# POWER.net
KiCad netlist of a schematic drawn in Altium Designer
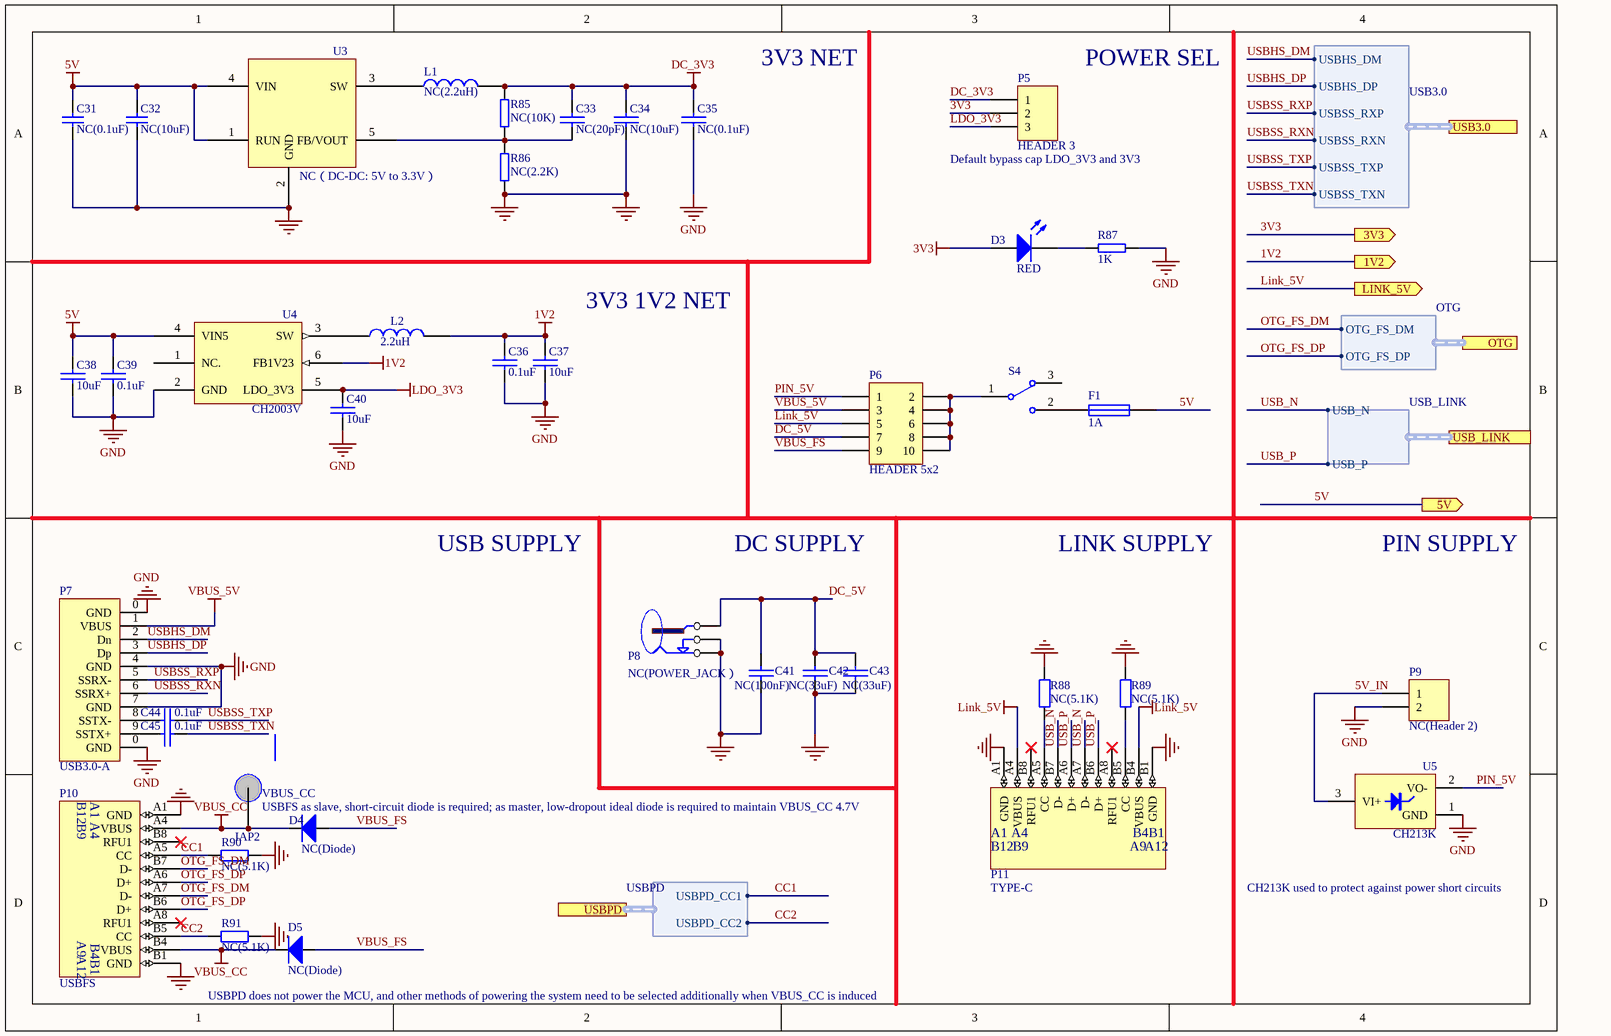
[diagram p0: POWER.SchDoc]

(export (version "E")
  (design (tool "Eeschema 10.0.6"))
  (components
    (comp (ref "C31")
      (value "NC(0.1uF)")
      (footprint "0402_C")
      (description "Capacitor")
      (fields (field (name "PUBLISHER") "Altium Limited"))
      (libsource (lib "Miscellaneous Devices") (part "Cap"))
    )
    (comp (ref "C32")
      (value "NC(10uF)")
      (footprint "0603_C")
      (description "Capacitor")
      (fields (field (name "PUBLISHER") "Altium Limited"))
      (libsource (lib "Miscellaneous Devices") (part "Cap"))
    )
    (comp (ref "C33")
      (value "NC(20pF)")
      (footprint "0402_C")
      (description "Capacitor")
      (libsource (lib "*") (part "CAP"))
    )
    (comp (ref "C34")
      (value "NC(10uF)")
      (footprint "0603_C")
      (description "Capacitor")
      (libsource (lib "*") (part "CAP"))
    )
    (comp (ref "C35")
      (value "NC(0.1uF)")
      (footprint "0402_C")
      (description "Capacitor")
      (libsource (lib "*") (part "CAP"))
    )
    (comp (ref "C36")
      (value "0.1uF")
      (footprint "0402_C")
      (description "Capacitor")
      (libsource (lib "") (part "CAP_1"))
    )
    (comp (ref "C37")
      (value "10uF")
      (footprint "0603_C")
      (description "Capacitor")
      (libsource (lib "*") (part "CAP"))
    )
    (comp (ref "C38")
      (value "10uF")
      (footprint "0603_C")
      (description "Capacitor")
      (libsource (lib "*") (part "CAP"))
    )
    (comp (ref "C39")
      (value "0.1uF")
      (footprint "0402_C")
      (description "Capacitor")
      (libsource (lib "") (part "CAP_1"))
    )
    (comp (ref "C40")
      (value "10uF")
      (footprint "0603_C")
      (description "Capacitor")
      (libsource (lib "*") (part "CAP"))
    )
    (comp (ref "C41")
      (value "NC(100nF)")
      (footprint "0402_C")
      (description "Capacitor")
      (libsource (lib "*") (part "CAP"))
    )
    (comp (ref "C42")
      (value "NC(33uF)")
      (footprint "3528_C")
      (description "Capacitor")
      (libsource (lib "*") (part "CAP"))
    )
    (comp (ref "C43")
      (value "NC(33uF)")
      (footprint "3528_C")
      (description "Capacitor")
      (libsource (lib "*") (part "CAP"))
    )
    (comp (ref "C44")
      (value "0.1uF")
      (footprint "0402_C")
      (description "Capacitor")
      (libsource (lib "*") (part "CAP"))
    )
    (comp (ref "C45")
      (value "0.1uF")
      (footprint "0402_C")
      (description "Capacitor")
      (libsource (lib "*") (part "CAP"))
    )
    (comp (ref "D3")
      (value "RED")
      (footprint "0603+")
      (description "Typical INFRARED GaAs LED")
      (fields (field (name "PUBLISHER") "Altium Limited"))
      (libsource (lib "*") (part "LED0"))
    )
    (comp (ref "D4")
      (value "NC(Diode)")
      (footprint "SOD-323")
      (description "Default Diode")
      (libsource (lib "wch_sch_others") (part "Diode"))
    )
    (comp (ref "D5")
      (value "NC(Diode)")
      (footprint "SOD-323")
      (description "Default Diode")
      (libsource (lib "wch_sch_others") (part "Diode"))
    )
    (comp (ref "F1")
      (value "1A")
      (footprint "0805")
      (description "Fuse")
      (libsource (lib "*") (part "FUSE1"))
    )
    (comp (ref "IAP2")
      (value "VBUS_CC")
      (footprint "TESTPOINT1")
      (description "测试点")
      (libsource (lib "wch_sch_others") (part "Testpoint"))
    )
    (comp (ref "L1") (value "NC(2.2uH)") (footprint "CD32") (libsource (lib "*") (part "INDUCTOR")))
    (comp (ref "L2") (value "2.2uH") (footprint "CD32") (libsource (lib "*") (part "INDUCTOR")))
    (comp (ref "P5")
      (value "HEADER 3")
      (footprint "SIP3-2.54MM")
      (description "Header, 3-Pin")
      (libsource (lib "wch_sch_others") (part "HEADER 3"))
    )
    (comp (ref "P6")
      (value "HEADER 5x2")
      (footprint "MYPCB:IDC10-2.54mm")
      (description "Header, 5-Pin, Dual row")
      (libsource (lib "wch_sch_others") (part "HEADER 5x2"))
    )
    (comp (ref "P7")
      (value "USB3.0-A")
      (footprint "USB3.0-A-Receptacle")
      (libsource (lib "wch_sch_others") (part "USB3.0-A"))
    )
    (comp (ref "P8") (value "NC(POWER_JACK）") (footprint "DC-005") (libsource (lib "*") (part "POWER_JACK")))
    (comp (ref "P9")
      (value "NC(Header 2)")
      (footprint "SIP2-2.54mm")
      (description "Header, 2-Pin")
      (fields (field (name "PUBLISHER") "Altium Limited"))
      (libsource (lib "*") (part "Header 2"))
    )
    (comp (ref "P10")
      (value "USBFS")
      (footprint "TYPE-C-Receptacle-2.0")
      (libsource (lib "*") (part "TYPE-C1"))
    )
    (comp (ref "P11")
      (value "TYPE-C")
      (footprint "TYPE-C-Receptacle-2.0")
      (libsource (lib "") (part "TYPE-C1_1"))
    )
    (comp (ref "R85") (value "NC(10K)") (footprint "0402") (libsource (lib "*") (part "R")))
    (comp (ref "R86") (value "NC(2.2K)") (footprint "0402") (libsource (lib "*") (part "R")))
    (comp (ref "R87") (value "1K") (footprint "0402") (libsource (lib "wch_sch_others") (part "RES")))
    (comp (ref "R88")
      (value "NC(5.1K)")
      (footprint "0402")
      (description "Resistor")
      (libsource (lib "Miscellaneous Devices") (part "Res2"))
    )
    (comp (ref "R89")
      (value "NC(5.1K)")
      (footprint "0402")
      (description "Resistor")
      (libsource (lib "Miscellaneous Devices") (part "Res2"))
    )
    (comp (ref "R90")
      (value "NC(5.1K)")
      (footprint "0402")
      (description "Resistor")
      (libsource (lib "") (part "Res2_1"))
    )
    (comp (ref "R91")
      (value "NC(5.1K)")
      (footprint "0402")
      (description "Resistor")
      (libsource (lib "") (part "Res2_1"))
    )
    (comp (ref "S4")
      (value "SW-SPDT")
      (footprint "SW1")
      (description "SPDT Subminiature Toggle Switch, Right Angle Mounting, Vertical Actuation")
      (libsource (lib "*") (part "SW-SPDT"))
    )
    (comp (ref "U3")
      (value "NC（DC-DC: 5V to 3.3V）")
      (footprint "SOT-23-5")
      (libsource (lib "SCH") (part "8503AM"))
    )
    (comp (ref "U4")
      (value "CH2003V")
      (footprint "SOT-23-6")
      (description "Step-Down DC-DC Converter, 5V input, 1.23V * 700mA output, with LDO 3.3V * 160mA")
      (libsource (lib "DHXXXSCH") (part "CH2003V"))
    )
    (comp (ref "U5")
      (value "CH213K")
      (footprint "SOT-23-3")
      (description "Ideal Diode 5V*1A")
      (libsource (lib "*") (part "CH213K"))
    )
  )
  (nets
    (net (code "5") (name "/5V_IN") (class "Default")
      (node (ref "P9") (pin "1") (pinfunction "1_1") (pintype "passive"))
      (node (ref "U5") (pin "3") (pinfunction "VI+_3") (pintype "power_in"))
    )
    (net (code "6") (name "/CC1") (class "Default")
      (node (ref "P10") (pin "A5") (pinfunction "CC_A5") (pintype "bidirectional"))
      (node (ref "R90") (pin "1") (pinfunction "1_1") (pintype "passive"))
    )
    (net (code "7") (name "/CC2") (class "Default")
      (node (ref "P10") (pin "B5") (pinfunction "CC_B5") (pintype "bidirectional"))
      (node (ref "R91") (pin "1") (pinfunction "1_1") (pintype "passive"))
    )
    (net (code "8") (name "/DC_5V") (class "Default")
      (node (ref "C41") (pin "2") (pinfunction "2_2") (pintype "passive"))
      (node (ref "C42") (pin "2") (pinfunction "2_2") (pintype "passive"))
      (node (ref "C43") (pin "2") (pinfunction "2_2") (pintype "passive"))
      (node (ref "P6") (pin "7") (pinfunction "7_7") (pintype "passive"))
      (node (ref "P8") (pin "1") (pinfunction "V_1") (pintype "passive"))
    )
    (net (code "9") (name "/OTG_FS_DM") (class "Default")
      (node (ref "P10") (pin "A7") (pinfunction "D-_A7") (pintype "bidirectional"))
      (node (ref "P10") (pin "B7") (pinfunction "D-_B7") (pintype "bidirectional"))
    )
    (net (code "10") (name "/OTG_FS_DP") (class "Default")
      (node (ref "P10") (pin "A6") (pinfunction "D+_A6") (pintype "bidirectional"))
      (node (ref "P10") (pin "B6") (pinfunction "D+_B6") (pintype "bidirectional"))
    )
    (net (code "11") (name "/PIN_5V") (class "Default")
      (node (ref "P6") (pin "1") (pinfunction "1_1") (pintype "passive"))
      (node (ref "U5") (pin "2") (pinfunction "VO-_2") (pintype "power_in"))
    )
    (net (code "12") (name "/USBHS_DM") (class "Default")
      (node (ref "P7") (pin "2") (pinfunction "Dn_2") (pintype "passive"))
    )
    (net (code "13") (name "/USBHS_DP") (class "Default")
      (node (ref "P7") (pin "3") (pinfunction "Dp_3") (pintype "passive"))
    )
    (net (code "14") (name "/USBSS_RXN") (class "Default")
      (node (ref "P7") (pin "6") (pinfunction "SSRX+_6") (pintype "passive"))
    )
    (net (code "15") (name "/USBSS_RXP") (class "Default")
      (node (ref "P7") (pin "5") (pinfunction "SSRX-_5") (pintype "passive"))
    )
    (net (code "16") (name "/USBSS_TXN") (class "Default")
      (node (ref "C45") (pin "2") (pinfunction "2_2") (pintype "passive"))
    )
    (net (code "17") (name "/USBSS_TXP") (class "Default")
      (node (ref "C44") (pin "2") (pinfunction "2_2") (pintype "passive"))
    )
    (net (code "18") (name "/USB_N") (class "Default")
      (node (ref "P11") (pin "A7") (pinfunction "D-_A7") (pintype "bidirectional"))
      (node (ref "P11") (pin "B7") (pinfunction "D-_B7") (pintype "bidirectional"))
    )
    (net (code "19") (name "/USB_P") (class "Default")
      (node (ref "P11") (pin "A6") (pinfunction "D+_A6") (pintype "bidirectional"))
      (node (ref "P11") (pin "B6") (pinfunction "D+_B6") (pintype "bidirectional"))
    )
    (net (code "20") (name "/VBUS_FS") (class "Default")
      (node (ref "D4") (pin "1") (pinfunction "A_1") (pintype "passive"))
      (node (ref "D5") (pin "1") (pinfunction "A_1") (pintype "passive"))
      (node (ref "P6") (pin "9") (pinfunction "9_9") (pintype "passive"))
    )
    (net (code "25") (name "1V2") (class "Default")
      (node (ref "C36") (pin "2") (pinfunction "2_2") (pintype "passive"))
      (node (ref "C37") (pin "2") (pinfunction "2_2") (pintype "passive"))
      (node (ref "L2") (pin "2") (pinfunction "2_2") (pintype "passive"))
      (node (ref "U4") (pin "6") (pinfunction "FB1V23_6") (pintype "input"))
    )
    (net (code "26") (name "3V3") (class "Default")
      (node (ref "D3") (pin "1") (pinfunction "A_1") (pintype "passive"))
      (node (ref "P5") (pin "2") (pinfunction "2_2") (pintype "passive"))
    )
    (net (code "27") (name "5V") (class "Default")
      (node (ref "C31") (pin "2") (pinfunction "2_2") (pintype "passive"))
      (node (ref "C32") (pin "2") (pinfunction "2_2") (pintype "passive"))
      (node (ref "C38") (pin "2") (pinfunction "2_2") (pintype "passive"))
      (node (ref "C39") (pin "2") (pinfunction "2_2") (pintype "passive"))
      (node (ref "F1") (pin "1") (pinfunction "1_1") (pintype "passive"))
      (node (ref "U3") (pin "1") (pinfunction "RUN_1") (pintype "passive"))
      (node (ref "U3") (pin "4") (pinfunction "VIN_4") (pintype "passive"))
      (node (ref "U4") (pin "4") (pinfunction "VIN5_4") (pintype "power_in"))
    )
    (net (code "28") (name "DC_3V3") (class "Default")
      (node (ref "C33") (pin "1") (pinfunction "1_1") (pintype "passive"))
      (node (ref "C34") (pin "1") (pinfunction "1_1") (pintype "passive"))
      (node (ref "C35") (pin "1") (pinfunction "1_1") (pintype "passive"))
      (node (ref "L1") (pin "2") (pinfunction "2_2") (pintype "passive"))
      (node (ref "P5") (pin "1") (pinfunction "1_1") (pintype "passive"))
      (node (ref "R85") (pin "1") (pinfunction "1_1") (pintype "passive"))
    )
    (net (code "29") (name "GND") (class "Default")
      (node (ref "C31") (pin "1") (pinfunction "1_1") (pintype "passive"))
      (node (ref "C32") (pin "1") (pinfunction "1_1") (pintype "passive"))
      (node (ref "C34") (pin "2") (pinfunction "2_2") (pintype "passive"))
      (node (ref "C35") (pin "2") (pinfunction "2_2") (pintype "passive"))
      (node (ref "C36") (pin "1") (pinfunction "1_1") (pintype "passive"))
      (node (ref "C37") (pin "1") (pinfunction "1_1") (pintype "passive"))
      (node (ref "C38") (pin "1") (pinfunction "1_1") (pintype "passive"))
      (node (ref "C39") (pin "1") (pinfunction "1_1") (pintype "passive"))
      (node (ref "C40") (pin "1") (pinfunction "1_1") (pintype "passive"))
      (node (ref "C41") (pin "1") (pinfunction "1_1") (pintype "passive"))
      (node (ref "C42") (pin "1") (pinfunction "1_1") (pintype "passive"))
      (node (ref "C43") (pin "1") (pinfunction "1_1") (pintype "passive"))
      (node (ref "P10") (pin "A1") (pinfunction "GND_A1") (pintype "bidirectional"))
      (node (ref "P10") (pin "B1") (pinfunction "GND_B1") (pintype "bidirectional"))
      (node (ref "P11") (pin "A1") (pinfunction "GND_A1") (pintype "bidirectional"))
      (node (ref "P11") (pin "B1") (pinfunction "GND_B1") (pintype "bidirectional"))
      (node (ref "P7") (pin "0") (pinfunction "GND_0") (pintype "passive"))
      (node (ref "P7") (pin "4") (pinfunction "GND_4") (pintype "passive"))
      (node (ref "P7") (pin "7") (pinfunction "GND_7") (pintype "passive"))
      (node (ref "P8") (pin "2") (pinfunction "G_2") (pintype "passive"))
      (node (ref "P8") (pin "3") (pinfunction "X_3") (pintype "passive"))
      (node (ref "P9") (pin "2") (pinfunction "2_2") (pintype "passive"))
      (node (ref "R86") (pin "1") (pinfunction "1_1") (pintype "passive"))
      (node (ref "R87") (pin "2") (pintype "passive"))
      (node (ref "R88") (pin "2") (pinfunction "2_2") (pintype "passive"))
      (node (ref "R89") (pin "2") (pinfunction "2_2") (pintype "passive"))
      (node (ref "R90") (pin "2") (pinfunction "2_2") (pintype "passive"))
      (node (ref "R91") (pin "2") (pinfunction "2_2") (pintype "passive"))
      (node (ref "U3") (pin "2") (pinfunction "GND_2") (pintype "passive"))
      (node (ref "U4") (pin "2") (pinfunction "GND_2") (pintype "power_in"))
      (node (ref "U5") (pin "1") (pinfunction "GND_1") (pintype "power_in"))
    )
    (net (code "30") (name "LDO_3V3") (class "Default")
      (node (ref "C40") (pin "2") (pinfunction "2_2") (pintype "passive"))
      (node (ref "P5") (pin "3") (pinfunction "3_3") (pintype "passive"))
      (node (ref "U4") (pin "5") (pinfunction "LDO_3V3_5") (pintype "power_in"))
    )
    (net (code "31") (name "Link_5V") (class "Default")
      (node (ref "P11") (pin "A4") (pinfunction "VBUS_A4") (pintype "bidirectional"))
      (node (ref "P11") (pin "B4") (pinfunction "VBUS_B4") (pintype "bidirectional"))
      (node (ref "P6") (pin "5") (pinfunction "5_5") (pintype "passive"))
    )
    (net (code "32") (name "Net-(D3-K)") (class "Default")
      (node (ref "D3") (pin "2") (pinfunction "K_2") (pintype "passive"))
      (node (ref "R87") (pin "1") (pintype "passive"))
    )
    (net (code "33") (name "Net-(F1-Pad2)") (class "Default")
      (node (ref "F1") (pin "2") (pinfunction "2_2") (pintype "passive"))
      (node (ref "S4") (pin "2") (pinfunction "2_2") (pintype "passive"))
    )
    (net (code "34") (name "Net-(P6-Pad10)") (class "Default")
      (node (ref "P6") (pin "10") (pinfunction "10_10") (pintype "passive"))
      (node (ref "P6") (pin "2") (pinfunction "2_2") (pintype "passive"))
      (node (ref "P6") (pin "4") (pinfunction "4_4") (pintype "passive"))
      (node (ref "P6") (pin "6") (pinfunction "6_6") (pintype "passive"))
      (node (ref "P6") (pin "8") (pinfunction "8_8") (pintype "passive"))
      (node (ref "S4") (pin "1") (pinfunction "1_1") (pintype "passive"))
    )
    (net (code "35") (name "Net-(P7-SSTX+)") (class "Default")
      (node (ref "C45") (pin "1") (pinfunction "1_1") (pintype "passive"))
      (node (ref "P7") (pin "9") (pinfunction "SSTX+_9") (pintype "passive"))
    )
    (net (code "36") (name "Net-(P7-SSTX-)") (class "Default")
      (node (ref "C44") (pin "1") (pinfunction "1_1") (pintype "passive"))
      (node (ref "P7") (pin "8") (pinfunction "SSTX-_8") (pintype "passive"))
    )
    (net (code "37") (name "Net-(P11-CC-PadA5)") (class "Default")
      (node (ref "P11") (pin "A5") (pinfunction "CC_A5") (pintype "bidirectional"))
      (node (ref "R88") (pin "1") (pinfunction "1_1") (pintype "passive"))
    )
    (net (code "38") (name "Net-(P11-CC-PadB5)") (class "Default")
      (node (ref "P11") (pin "B5") (pinfunction "CC_B5") (pintype "bidirectional"))
      (node (ref "R89") (pin "1") (pinfunction "1_1") (pintype "passive"))
    )
    (net (code "39") (name "Net-(U3-FB{slash}VOUT)") (class "Default")
      (node (ref "C33") (pin "2") (pinfunction "2_2") (pintype "passive"))
      (node (ref "R85") (pin "2") (pinfunction "2_2") (pintype "passive"))
      (node (ref "R86") (pin "2") (pinfunction "2_2") (pintype "passive"))
      (node (ref "U3") (pin "5") (pinfunction "FB/VOUT_5") (pintype "passive"))
    )
    (net (code "40") (name "Net-(U3-SW)") (class "Default")
      (node (ref "L1") (pin "1") (pinfunction "1_1") (pintype "passive"))
      (node (ref "U3") (pin "3") (pinfunction "SW_3") (pintype "passive"))
    )
    (net (code "41") (name "Net-(U4-SW)") (class "Default")
      (node (ref "L2") (pin "1") (pinfunction "1_1") (pintype "passive"))
      (node (ref "U4") (pin "3") (pinfunction "SW_3") (pintype "output"))
    )
    (net (code "42") (name "VBUS_5V") (class "Default")
      (node (ref "P6") (pin "3") (pinfunction "3_3") (pintype "passive"))
      (node (ref "P7") (pin "1") (pinfunction "VBUS_1") (pintype "passive"))
    )
    (net (code "43") (name "VBUS_CC") (class "Default")
      (node (ref "D4") (pin "2") (pinfunction "K_2") (pintype "passive"))
      (node (ref "D5") (pin "2") (pinfunction "K_2") (pintype "passive"))
      (node (ref "IAP2") (pin "1") (pinfunction "point_1") (pintype "passive"))
      (node (ref "P10") (pin "A4") (pinfunction "VBUS_A4") (pintype "bidirectional"))
      (node (ref "P10") (pin "B4") (pinfunction "VBUS_B4") (pintype "bidirectional"))
    )
    (net (code "44") (name "unconnected-(P10-RFU1-PadA8)") (class "Default")
      (node (ref "P10") (pin "A8") (pinfunction "RFU1_A8") (pintype "bidirectional+no_connect"))
    )
    (net (code "45") (name "unconnected-(P10-RFU1-PadB8)") (class "Default")
      (node (ref "P10") (pin "B8") (pinfunction "RFU1_B8") (pintype "bidirectional+no_connect"))
    )
    (net (code "46") (name "unconnected-(P11-RFU1-PadA8)") (class "Default")
      (node (ref "P11") (pin "A8") (pinfunction "RFU1_A8") (pintype "bidirectional+no_connect"))
    )
    (net (code "47") (name "unconnected-(P11-RFU1-PadB8)") (class "Default")
      (node (ref "P11") (pin "B8") (pinfunction "RFU1_B8") (pintype "bidirectional+no_connect"))
    )
    (net (code "48") (name "unconnected-(S4-Pad3)") (class "Default")
      (node (ref "S4") (pin "3") (pinfunction "3_3") (pintype "passive"))
    )
    (net (code "49") (name "unconnected-(U4-NC.-Pad1)") (class "Default")
      (node (ref "U4") (pin "1") (pinfunction "NC._1") (pintype "passive"))
    )
  )
)
